# IMU_SMD.net
KiCad netlist of a schematic drawn in EAGLE
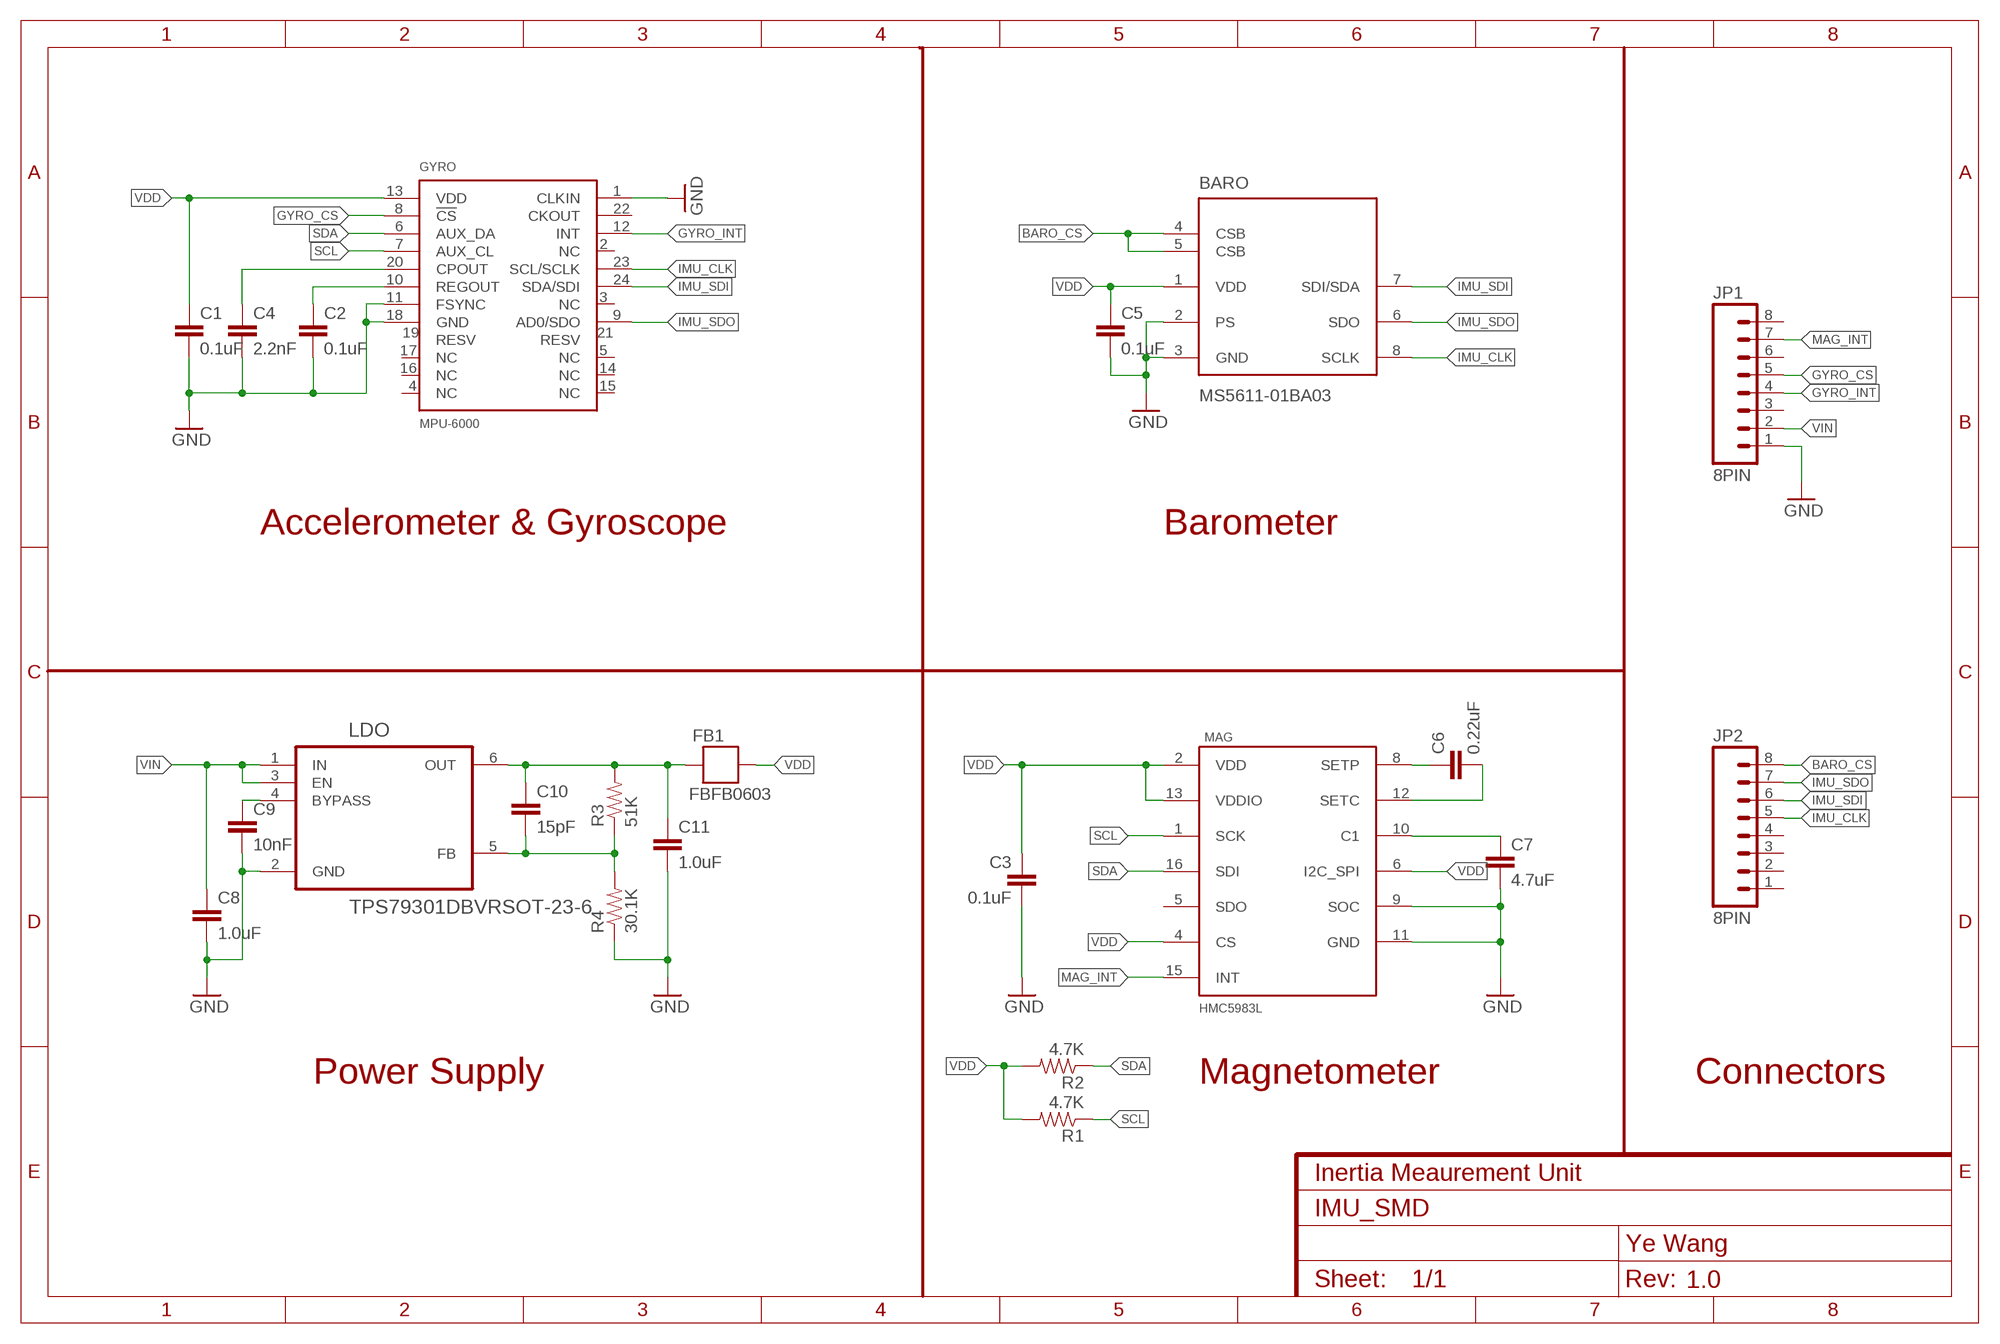
[diagram p0: schematic, sheet 1]

(export (version "E")
  (design (tool "Eeschema 10.0.6"))
  (components
    (comp (ref "BARO")
      (value "MS5611-01BA03")
      (footprint "eagle-import:SON125P300X500X100-8N")
      (libsource (lib "eagle-import") (part "MS5611-01BA03"))
    )
    (comp (ref "C1")
      (value "0.1uF")
      (footprint "eagle-import:0603-CAP")
      (libsource (lib "eagle-import") (part "0.1UF-25V-5%(0603)"))
    )
    (comp (ref "C2")
      (value "0.1uF")
      (footprint "eagle-import:0603-CAP")
      (libsource (lib "eagle-import") (part "0.1UF-25V-5%(0603)"))
    )
    (comp (ref "C3")
      (value "0.1uF")
      (footprint "eagle-import:0603-CAP")
      (libsource (lib "eagle-import") (part "0.1UF-25V-5%(0603)"))
    )
    (comp (ref "C4")
      (value "2.2nF")
      (footprint "eagle-import:0603-CAP")
      (libsource (lib "eagle-import") (part "2.2NF/2200PF-50V-10%(0603)"))
    )
    (comp (ref "C5")
      (value "0.1uF")
      (footprint "eagle-import:0603-CAP")
      (libsource (lib "eagle-import") (part "0.1UF-25V-5%(0603)"))
    )
    (comp (ref "C6")
      (value "0.22uF")
      (footprint "eagle-import:0603-CAP")
      (libsource (lib "eagle-import") (part "0.22UF-25V-10%(0603)"))
    )
    (comp (ref "C7")
      (value "4.7uF")
      (footprint "eagle-import:0603-CAP")
      (libsource (lib "eagle-import") (part "4.7UF-6.3V-10%(0603)0603"))
    )
    (comp (ref "C8")
      (value "1.0uF")
      (footprint "eagle-import:0603-CAP")
      (libsource (lib "eagle-import") (part "1.0UF-16V-10%(0603)"))
    )
    (comp (ref "C9")
      (value "10nF")
      (footprint "eagle-import:0603-CAP")
      (libsource (lib "eagle-import") (part "0.1UF-25V-5%(0603)"))
    )
    (comp (ref "C10")
      (value "15pF")
      (footprint "eagle-import:0603-CAP")
      (libsource (lib "eagle-import") (part "15PF-50V-5%(0603)"))
    )
    (comp (ref "C11")
      (value "1.0uF")
      (footprint "eagle-import:0603-CAP")
      (libsource (lib "eagle-import") (part "1.0UF-16V-10%(0603)"))
    )
    (comp (ref "FB1")
      (value "FBFB0603")
      (footprint "eagle-import:0603")
      (libsource (lib "eagle-import") (part "FBFB0603"))
    )
    (comp (ref "GYRO")
      (value "MPU-6000")
      (footprint "eagle-import:QFN24-NO-PAD")
      (libsource (lib "eagle-import") (part "MPU-6000"))
    )
    (comp (ref "JP1")
      (value "8PIN")
      (footprint "eagle-import:1X08_SQE_NO_SILK")
      (libsource (lib "eagle-import") (part "M08SQE"))
    )
    (comp (ref "JP2")
      (value "8PIN")
      (footprint "eagle-import:1X08_SQE_NO_SILK")
      (libsource (lib "eagle-import") (part "M08SQE"))
    )
    (comp (ref "LDO")
      (value "TPS79301DBVRSOT-23-6")
      (footprint "eagle-import:SOT95P280X145-6N")
      (fields (field (name "MPN") "TPS79301DBVR"))
      (libsource (lib "eagle-import") (part "TPS79301DBVRSOT-23-6"))
    )
    (comp (ref "MAG")
      (value "HMC5983L")
      (footprint "eagle-import:LPCC16")
      (libsource (lib "eagle-import") (part "HMC5983L"))
    )
    (comp (ref "R1")
      (value "4.7K")
      (footprint "eagle-import:0603-RES")
      (libsource (lib "eagle-import") (part "RESISTOR0603-RES"))
    )
    (comp (ref "R2")
      (value "4.7K")
      (footprint "eagle-import:0603-RES")
      (libsource (lib "eagle-import") (part "RESISTOR0603-RES"))
    )
    (comp (ref "R3")
      (value "51K")
      (footprint "eagle-import:0603-RES")
      (libsource (lib "eagle-import") (part "RESISTOR0603-RES"))
    )
    (comp (ref "R4")
      (value "30.1K")
      (footprint "eagle-import:0603-RES")
      (libsource (lib "eagle-import") (part "RESISTOR0603-RES"))
    )
  )
  (nets
    (net (code "1") (name "BARO_CS") (class "Default")
      (node (ref "BARO") (pin "4") (pinfunction "CSB_4") (pintype "input"))
      (node (ref "BARO") (pin "5") (pinfunction "CSB_5") (pintype "input"))
      (node (ref "JP2") (pin "8") (pinfunction "8_8") (pintype "passive"))
    )
    (net (code "2") (name "GND") (class "Default")
      (node (ref "BARO") (pin "2") (pinfunction "PS_2") (pintype "input"))
      (node (ref "BARO") (pin "3") (pinfunction "GND_3") (pintype "power_in"))
      (node (ref "C1") (pin "2") (pinfunction "2_2") (pintype "passive"))
      (node (ref "C11") (pin "2") (pinfunction "2_2") (pintype "passive"))
      (node (ref "C2") (pin "2") (pinfunction "2_2") (pintype "passive"))
      (node (ref "C3") (pin "2") (pinfunction "2_2") (pintype "passive"))
      (node (ref "C4") (pin "2") (pinfunction "2_2") (pintype "passive"))
      (node (ref "C5") (pin "2") (pinfunction "2_2") (pintype "passive"))
      (node (ref "C7") (pin "2") (pinfunction "2_2") (pintype "passive"))
      (node (ref "C8") (pin "2") (pinfunction "2_2") (pintype "passive"))
      (node (ref "C9") (pin "2") (pinfunction "2_2") (pintype "passive"))
      (node (ref "GYRO") (pin "1") (pinfunction "CLKIN_1") (pintype "bidirectional"))
      (node (ref "GYRO") (pin "11") (pinfunction "FSYNC_11") (pintype "bidirectional"))
      (node (ref "GYRO") (pin "18") (pinfunction "GND_18") (pintype "bidirectional"))
      (node (ref "JP1") (pin "1") (pinfunction "1_1") (pintype "passive"))
      (node (ref "LDO") (pin "2") (pinfunction "GND_2") (pintype "passive"))
      (node (ref "MAG") (pin "11") (pinfunction "GND_11") (pintype "bidirectional"))
      (node (ref "MAG") (pin "9") (pinfunction "SOC_9") (pintype "bidirectional"))
      (node (ref "R4") (pin "1") (pinfunction "1_1") (pintype "passive"))
    )
    (net (code "3") (name "GYRO_CS") (class "Default")
      (node (ref "GYRO") (pin "8") (pinfunction "~{CS}_8") (pintype "bidirectional"))
      (node (ref "JP1") (pin "5") (pinfunction "5_5") (pintype "passive"))
    )
    (net (code "4") (name "GYRO_INT") (class "Default")
      (node (ref "GYRO") (pin "12") (pinfunction "INT_12") (pintype "bidirectional"))
      (node (ref "JP1") (pin "4") (pinfunction "4_4") (pintype "passive"))
    )
    (net (code "5") (name "IMU_CLK") (class "Default")
      (node (ref "BARO") (pin "8") (pinfunction "SCLK_8") (pintype "input"))
      (node (ref "GYRO") (pin "23") (pinfunction "SCL/SCLK_23") (pintype "bidirectional"))
      (node (ref "JP2") (pin "5") (pinfunction "5_5") (pintype "passive"))
    )
    (net (code "6") (name "IMU_SDI") (class "Default")
      (node (ref "BARO") (pin "7") (pinfunction "SDI/SDA_7") (pintype "bidirectional"))
      (node (ref "GYRO") (pin "24") (pinfunction "SDA/SDI_24") (pintype "bidirectional"))
      (node (ref "JP2") (pin "6") (pinfunction "6_6") (pintype "passive"))
    )
    (net (code "7") (name "IMU_SDO") (class "Default")
      (node (ref "BARO") (pin "6") (pinfunction "SDO_6") (pintype "output"))
      (node (ref "GYRO") (pin "9") (pinfunction "AD0/SDO_9") (pintype "bidirectional"))
      (node (ref "JP2") (pin "7") (pinfunction "7_7") (pintype "passive"))
    )
    (net (code "8") (name "MAG_INT") (class "Default")
      (node (ref "JP1") (pin "7") (pinfunction "7_7") (pintype "passive"))
      (node (ref "MAG") (pin "15") (pinfunction "INT_15") (pintype "bidirectional"))
    )
    (net (code "9") (name "Net-(FB1-P$2)") (class "Default")
      (node (ref "C10") (pin "1") (pinfunction "1_1") (pintype "passive"))
      (node (ref "C11") (pin "1") (pinfunction "1_1") (pintype "passive"))
      (node (ref "FB1") (pin "2") (pinfunction "P$2_2") (pintype "bidirectional"))
      (node (ref "LDO") (pin "6") (pinfunction "OUT_6") (pintype "output"))
      (node (ref "R3") (pin "2") (pinfunction "2_2") (pintype "passive"))
    )
    (net (code "10") (name "Net-(GYRO-CPOUT)") (class "Default")
      (node (ref "C4") (pin "1") (pinfunction "1_1") (pintype "passive"))
      (node (ref "GYRO") (pin "20") (pinfunction "CPOUT_20") (pintype "bidirectional"))
    )
    (net (code "11") (name "Net-(GYRO-REGOUT)") (class "Default")
      (node (ref "C2") (pin "1") (pinfunction "1_1") (pintype "passive"))
      (node (ref "GYRO") (pin "10") (pinfunction "REGOUT_10") (pintype "bidirectional"))
    )
    (net (code "12") (name "Net-(LDO-BYPASS)") (class "Default")
      (node (ref "C9") (pin "1") (pinfunction "1_1") (pintype "passive"))
      (node (ref "LDO") (pin "4") (pinfunction "BYPASS_4") (pintype "input"))
    )
    (net (code "13") (name "Net-(LDO-FB)") (class "Default")
      (node (ref "C10") (pin "2") (pinfunction "2_2") (pintype "passive"))
      (node (ref "LDO") (pin "5") (pinfunction "FB_5") (pintype "input"))
      (node (ref "R3") (pin "1") (pinfunction "1_1") (pintype "passive"))
      (node (ref "R4") (pin "2") (pinfunction "2_2") (pintype "passive"))
    )
    (net (code "14") (name "Net-(MAG-C1)") (class "Default")
      (node (ref "C7") (pin "1") (pinfunction "1_1") (pintype "passive"))
      (node (ref "MAG") (pin "10") (pinfunction "C1_10") (pintype "bidirectional"))
    )
    (net (code "15") (name "Net-(MAG-SETC)") (class "Default")
      (node (ref "C6") (pin "2") (pinfunction "2_2") (pintype "passive"))
      (node (ref "MAG") (pin "12") (pinfunction "SETC_12") (pintype "bidirectional"))
    )
    (net (code "16") (name "Net-(MAG-SETP)") (class "Default")
      (node (ref "C6") (pin "1") (pinfunction "1_1") (pintype "passive"))
      (node (ref "MAG") (pin "8") (pinfunction "SETP_8") (pintype "bidirectional"))
    )
    (net (code "17") (name "SCL") (class "Default")
      (node (ref "GYRO") (pin "7") (pinfunction "AUX_CL_7") (pintype "bidirectional"))
      (node (ref "MAG") (pin "1") (pinfunction "SCK_1") (pintype "bidirectional"))
      (node (ref "R1") (pin "1") (pinfunction "1_1") (pintype "passive"))
    )
    (net (code "18") (name "SDA") (class "Default")
      (node (ref "GYRO") (pin "6") (pinfunction "AUX_DA_6") (pintype "bidirectional"))
      (node (ref "MAG") (pin "16") (pinfunction "SDI_16") (pintype "bidirectional"))
      (node (ref "R2") (pin "1") (pinfunction "1_1") (pintype "passive"))
    )
    (net (code "19") (name "VDD") (class "Default")
      (node (ref "BARO") (pin "1") (pinfunction "VDD_1") (pintype "power_in"))
      (node (ref "C1") (pin "1") (pinfunction "1_1") (pintype "passive"))
      (node (ref "C3") (pin "1") (pinfunction "1_1") (pintype "passive"))
      (node (ref "C5") (pin "1") (pinfunction "1_1") (pintype "passive"))
      (node (ref "FB1") (pin "1") (pinfunction "P$1_1") (pintype "bidirectional"))
      (node (ref "GYRO") (pin "13") (pinfunction "VDD_13") (pintype "bidirectional"))
      (node (ref "MAG") (pin "13") (pinfunction "VDDIO_13") (pintype "bidirectional"))
      (node (ref "MAG") (pin "2") (pinfunction "VDD_2") (pintype "bidirectional"))
      (node (ref "MAG") (pin "4") (pinfunction "CS_4") (pintype "bidirectional"))
      (node (ref "MAG") (pin "6") (pinfunction "I2C_SPI_6") (pintype "bidirectional"))
      (node (ref "R1") (pin "2") (pinfunction "2_2") (pintype "passive"))
      (node (ref "R2") (pin "2") (pinfunction "2_2") (pintype "passive"))
    )
    (net (code "20") (name "VIN") (class "Default")
      (node (ref "C8") (pin "1") (pinfunction "1_1") (pintype "passive"))
      (node (ref "JP1") (pin "2") (pinfunction "2_2") (pintype "passive"))
      (node (ref "LDO") (pin "1") (pinfunction "IN_1") (pintype "input"))
      (node (ref "LDO") (pin "3") (pinfunction "EN_3") (pintype "input"))
    )
    (net (code "21") (name "unconnected-(GYRO-CKOUT-Pad22)") (class "Default")
      (node (ref "GYRO") (pin "22") (pinfunction "CKOUT_22") (pintype "bidirectional"))
    )
    (net (code "22") (name "unconnected-(GYRO-NC-Pad2)") (class "Default")
      (node (ref "GYRO") (pin "2") (pinfunction "NC_2") (pintype "bidirectional"))
    )
    (net (code "23") (name "unconnected-(GYRO-NC-Pad3)") (class "Default")
      (node (ref "GYRO") (pin "3") (pinfunction "NC_3") (pintype "bidirectional"))
    )
    (net (code "24") (name "unconnected-(GYRO-NC-Pad4)") (class "Default")
      (node (ref "GYRO") (pin "4") (pinfunction "NC_4") (pintype "bidirectional"))
    )
    (net (code "25") (name "unconnected-(GYRO-NC-Pad5)") (class "Default")
      (node (ref "GYRO") (pin "5") (pinfunction "NC_5") (pintype "bidirectional"))
    )
    (net (code "26") (name "unconnected-(GYRO-NC-Pad14)") (class "Default")
      (node (ref "GYRO") (pin "14") (pinfunction "NC_14") (pintype "bidirectional"))
    )
    (net (code "27") (name "unconnected-(GYRO-NC-Pad15)") (class "Default")
      (node (ref "GYRO") (pin "15") (pinfunction "NC_15") (pintype "bidirectional"))
    )
    (net (code "28") (name "unconnected-(GYRO-NC-Pad16)") (class "Default")
      (node (ref "GYRO") (pin "16") (pinfunction "NC_16") (pintype "bidirectional"))
    )
    (net (code "29") (name "unconnected-(GYRO-NC-Pad17)") (class "Default")
      (node (ref "GYRO") (pin "17") (pinfunction "NC_17") (pintype "bidirectional"))
    )
    (net (code "30") (name "unconnected-(GYRO-RESV-Pad19)") (class "Default")
      (node (ref "GYRO") (pin "19") (pinfunction "RESV_19") (pintype "bidirectional"))
    )
    (net (code "31") (name "unconnected-(GYRO-RESV-Pad21)") (class "Default")
      (node (ref "GYRO") (pin "21") (pinfunction "RESV_21") (pintype "bidirectional"))
    )
    (net (code "32") (name "unconnected-(JP1-Pad3)") (class "Default")
      (node (ref "JP1") (pin "3") (pinfunction "3_3") (pintype "passive"))
    )
    (net (code "33") (name "unconnected-(JP1-Pad6)") (class "Default")
      (node (ref "JP1") (pin "6") (pinfunction "6_6") (pintype "passive"))
    )
    (net (code "34") (name "unconnected-(JP1-Pad8)") (class "Default")
      (node (ref "JP1") (pin "8") (pinfunction "8_8") (pintype "passive"))
    )
    (net (code "35") (name "unconnected-(JP2-Pad1)") (class "Default")
      (node (ref "JP2") (pin "1") (pinfunction "1_1") (pintype "passive"))
    )
    (net (code "36") (name "unconnected-(JP2-Pad2)") (class "Default")
      (node (ref "JP2") (pin "2") (pinfunction "2_2") (pintype "passive"))
    )
    (net (code "37") (name "unconnected-(JP2-Pad3)") (class "Default")
      (node (ref "JP2") (pin "3") (pinfunction "3_3") (pintype "passive"))
    )
    (net (code "38") (name "unconnected-(JP2-Pad4)") (class "Default")
      (node (ref "JP2") (pin "4") (pinfunction "4_4") (pintype "passive"))
    )
    (net (code "39") (name "unconnected-(MAG-SDO-Pad5)") (class "Default")
      (node (ref "MAG") (pin "5") (pinfunction "SDO_5") (pintype "bidirectional"))
    )
  )
)
